# Power-Supply.net
KiCad netlist of a schematic drawn in Altium Designer
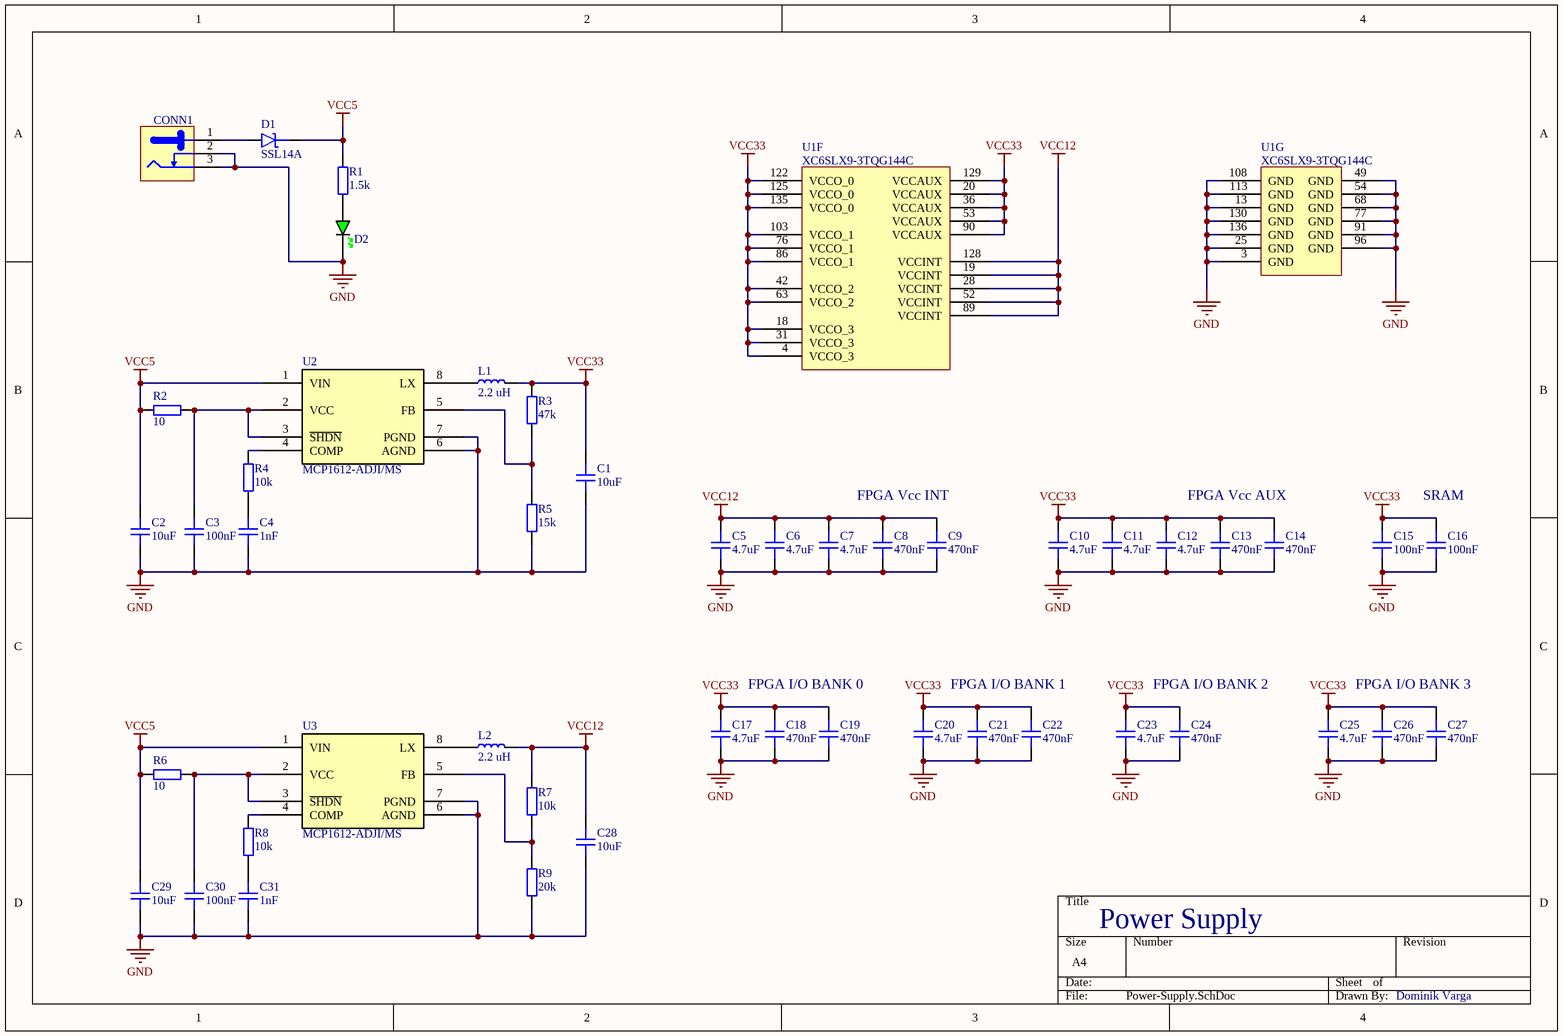
[diagram p0: Power-Supply.SchDoc]

(export (version "E")
  (design (tool "Eeschema 10.0.6"))
  (components
    (comp (ref "C1")
      (value "10uF")
      (footprint "CAP_SMD1210")
      (description "Capacitor SMD 1210")
      (libsource (lib "NES-Components") (part "CAP_1210"))
    )
    (comp (ref "C2")
      (value "10uF")
      (footprint "CAP_SMD1210")
      (description "Capacitor SMD 1210")
      (libsource (lib "NES-Components") (part "CAP_1210"))
    )
    (comp (ref "C3")
      (value "100nF")
      (footprint "CAP_SMD0603")
      (description "Capacitor SMD 0603")
      (libsource (lib "NES-Components") (part "CAP_0603"))
    )
    (comp (ref "C4")
      (value "1nF")
      (footprint "CAP_SMD0603")
      (description "Capacitor SMD 0603")
      (libsource (lib "NES-Components") (part "CAP_0603"))
    )
    (comp (ref "C5")
      (value "4.7uF")
      (footprint "CAP_SMD0603")
      (description "Capacitor SMD 0603")
      (libsource (lib "NES-Components") (part "CAP_0603"))
    )
    (comp (ref "C6")
      (value "4.7uF")
      (footprint "CAP_SMD0603")
      (description "Capacitor SMD 0603")
      (libsource (lib "NES-Components") (part "CAP_0603"))
    )
    (comp (ref "C7")
      (value "4.7uF")
      (footprint "CAP_SMD0603")
      (description "Capacitor SMD 0603")
      (libsource (lib "NES-Components") (part "CAP_0603"))
    )
    (comp (ref "C8")
      (value "470nF")
      (footprint "CAP_SMD0603")
      (description "Capacitor SMD 0603")
      (libsource (lib "NES-Components") (part "CAP_0603"))
    )
    (comp (ref "C9")
      (value "470nF")
      (footprint "CAP_SMD0603")
      (description "Capacitor SMD 0603")
      (libsource (lib "NES-Components") (part "CAP_0603"))
    )
    (comp (ref "C10")
      (value "4.7uF")
      (footprint "CAP_SMD0603")
      (description "Capacitor SMD 0603")
      (libsource (lib "NES-Components") (part "CAP_0603"))
    )
    (comp (ref "C11")
      (value "4.7uF")
      (footprint "CAP_SMD0603")
      (description "Capacitor SMD 0603")
      (libsource (lib "NES-Components") (part "CAP_0603"))
    )
    (comp (ref "C12")
      (value "4.7uF")
      (footprint "CAP_SMD0603")
      (description "Capacitor SMD 0603")
      (libsource (lib "NES-Components") (part "CAP_0603"))
    )
    (comp (ref "C13")
      (value "470nF")
      (footprint "CAP_SMD0603")
      (description "Capacitor SMD 0603")
      (libsource (lib "NES-Components") (part "CAP_0603"))
    )
    (comp (ref "C14")
      (value "470nF")
      (footprint "CAP_SMD0603")
      (description "Capacitor SMD 0603")
      (libsource (lib "NES-Components") (part "CAP_0603"))
    )
    (comp (ref "C15")
      (value "100nF")
      (footprint "CAP_SMD0603")
      (description "Capacitor SMD 0603")
      (libsource (lib "NES-Components") (part "CAP_0603"))
    )
    (comp (ref "C16")
      (value "100nF")
      (footprint "CAP_SMD0603")
      (description "Capacitor SMD 0603")
      (libsource (lib "NES-Components") (part "CAP_0603"))
    )
    (comp (ref "C17")
      (value "4.7uF")
      (footprint "CAP_SMD0603")
      (description "Capacitor SMD 0603")
      (libsource (lib "NES-Components") (part "CAP_0603"))
    )
    (comp (ref "C18")
      (value "470nF")
      (footprint "CAP_SMD0603")
      (description "Capacitor SMD 0603")
      (libsource (lib "NES-Components") (part "CAP_0603"))
    )
    (comp (ref "C19")
      (value "470nF")
      (footprint "CAP_SMD0603")
      (description "Capacitor SMD 0603")
      (libsource (lib "NES-Components") (part "CAP_0603"))
    )
    (comp (ref "C20")
      (value "4.7uF")
      (footprint "CAP_SMD0603")
      (description "Capacitor SMD 0603")
      (libsource (lib "NES-Components") (part "CAP_0603"))
    )
    (comp (ref "C21")
      (value "470nF")
      (footprint "CAP_SMD0603")
      (description "Capacitor SMD 0603")
      (libsource (lib "NES-Components") (part "CAP_0603"))
    )
    (comp (ref "C22")
      (value "470nF")
      (footprint "CAP_SMD0603")
      (description "Capacitor SMD 0603")
      (libsource (lib "NES-Components") (part "CAP_0603"))
    )
    (comp (ref "C23")
      (value "4.7uF")
      (footprint "CAP_SMD0603")
      (description "Capacitor SMD 0603")
      (libsource (lib "NES-Components") (part "CAP_0603"))
    )
    (comp (ref "C24")
      (value "470nF")
      (footprint "CAP_SMD0603")
      (description "Capacitor SMD 0603")
      (libsource (lib "NES-Components") (part "CAP_0603"))
    )
    (comp (ref "C25")
      (value "4.7uF")
      (footprint "CAP_SMD0603")
      (description "Capacitor SMD 0603")
      (libsource (lib "NES-Components") (part "CAP_0603"))
    )
    (comp (ref "C26")
      (value "470nF")
      (footprint "CAP_SMD0603")
      (description "Capacitor SMD 0603")
      (libsource (lib "NES-Components") (part "CAP_0603"))
    )
    (comp (ref "C27")
      (value "470nF")
      (footprint "CAP_SMD0603")
      (description "Capacitor SMD 0603")
      (libsource (lib "NES-Components") (part "CAP_0603"))
    )
    (comp (ref "C28")
      (value "10uF")
      (footprint "CAP_SMD1210")
      (description "Capacitor SMD 1210")
      (libsource (lib "NES-Components") (part "CAP_1210"))
    )
    (comp (ref "C29")
      (value "10uF")
      (footprint "CAP_SMD1210")
      (description "Capacitor SMD 1210")
      (libsource (lib "NES-Components") (part "CAP_1210"))
    )
    (comp (ref "C30")
      (value "100nF")
      (footprint "CAP_SMD0603")
      (description "Capacitor SMD 0603")
      (libsource (lib "NES-Components") (part "CAP_0603"))
    )
    (comp (ref "C31")
      (value "1nF")
      (footprint "CAP_SMD0603")
      (description "Capacitor SMD 0603")
      (libsource (lib "NES-Components") (part "CAP_0603"))
    )
    (comp (ref "CONN1")
      (value "DC_PWR")
      (footprint "DC_PWR_CONN")
      (description "12V /  5A, 2.1mm Diameter Pin, DC Power Socket With  Switch. DC10A Type")
      (libsource (lib "NES-Components") (part "DC_PWR"))
    )
    (comp (ref "D1")
      (value "SSL14A")
      (footprint "DIOM5226X230N")
      (description "Schottky Barrier Diode SSL14A")
      (libsource (lib "NES-Components") (part "SSL14A"))
    )
    (comp (ref "D2")
      (value "GREEN")
      (footprint "LED_G_SMD0603")
      (description "LED 0603 GREEN SMD")
      (libsource (lib "NES-Components") (part "LED_0603_GREEN"))
    )
    (comp (ref "L1")
      (value "2.2 uH")
      (footprint "SDR0604")
      (description "Inductor SDR0604")
      (libsource (lib "NES-Components") (part "SDR0604"))
    )
    (comp (ref "L2")
      (value "2.2 uH")
      (footprint "SDR0604")
      (description "Inductor SDR0604")
      (libsource (lib "NES-Components") (part "SDR0604"))
    )
    (comp (ref "R1")
      (value "1.5k")
      (footprint "RES_SMD0603")
      (description "Resistor SMD 0603")
      (libsource (lib "NES-Components") (part "RES_0603"))
    )
    (comp (ref "R2")
      (value "10")
      (footprint "RES_SMD0603")
      (description "Resistor SMD 0603")
      (libsource (lib "NES-Components") (part "RES_0603"))
    )
    (comp (ref "R3")
      (value "47k")
      (footprint "RES_SMD0603")
      (description "Resistor SMD 0603")
      (libsource (lib "NES-Components") (part "RES_0603"))
    )
    (comp (ref "R4")
      (value "10k")
      (footprint "RES_SMD0603")
      (description "Resistor SMD 0603")
      (libsource (lib "NES-Components") (part "RES_0603"))
    )
    (comp (ref "R5")
      (value "15k")
      (footprint "RES_SMD0603")
      (description "Resistor SMD 0603")
      (libsource (lib "NES-Components") (part "RES_0603"))
    )
    (comp (ref "R6")
      (value "10")
      (footprint "RES_SMD0603")
      (description "Resistor SMD 0603")
      (libsource (lib "NES-Components") (part "RES_0603"))
    )
    (comp (ref "R7")
      (value "10k")
      (footprint "RES_SMD0603")
      (description "Resistor SMD 0603")
      (libsource (lib "NES-Components") (part "RES_0603"))
    )
    (comp (ref "R8")
      (value "10k")
      (footprint "RES_SMD0603")
      (description "Resistor SMD 0603")
      (libsource (lib "NES-Components") (part "RES_0603"))
    )
    (comp (ref "R9")
      (value "20k")
      (footprint "RES_SMD0603")
      (description "Resistor SMD 0603")
      (libsource (lib "NES-Components") (part "RES_0603"))
    )
    (comp (ref "U1")
      (value "XC6SLX9-3TQG144C")
      (footprint "QFP50P2200X2200X160-144N")
      (libsource (lib "NES-Components") (part "XC6SLX9-3TQG144C"))
    )
    (comp (ref "U2")
      (value "MCP1612-ADJI/MS")
      (footprint "SOP65P490X109-8N")
      (description "Single 1A Synchronous Buck Regulator, 1.4MHz, 8-Pin MSOP, Industrial Temperature")
      (fields (field (name "COPYRIGHT") "Copyright (C) 2023 Ultra Librarian. All rights reserved."))
      (libsource (lib "NES-Components") (part "MCP1612-ADJI/MS"))
    )
    (comp (ref "U3")
      (value "MCP1612-ADJI/MS")
      (footprint "SOP65P490X109-8N")
      (description "Single 1A Synchronous Buck Regulator, 1.4MHz, 8-Pin MSOP, Industrial Temperature")
      (fields (field (name "COPYRIGHT") "Copyright (C) 2023 Ultra Librarian. All rights reserved."))
      (libsource (lib "NES-Components") (part "MCP1612-ADJI/MS"))
    )
  )
  (nets
    (net (code "1") (name "GND") (class "Default")
      (node (ref "C1") (pin "1") (pinfunction "1_1") (pintype "passive"))
      (node (ref "C10") (pin "1") (pinfunction "1_1") (pintype "passive"))
      (node (ref "C11") (pin "1") (pinfunction "1_1") (pintype "passive"))
      (node (ref "C12") (pin "1") (pinfunction "1_1") (pintype "passive"))
      (node (ref "C13") (pin "1") (pinfunction "1_1") (pintype "passive"))
      (node (ref "C14") (pin "1") (pinfunction "1_1") (pintype "passive"))
      (node (ref "C15") (pin "1") (pinfunction "1_1") (pintype "passive"))
      (node (ref "C16") (pin "1") (pinfunction "1_1") (pintype "passive"))
      (node (ref "C17") (pin "1") (pinfunction "1_1") (pintype "passive"))
      (node (ref "C18") (pin "1") (pinfunction "1_1") (pintype "passive"))
      (node (ref "C19") (pin "1") (pinfunction "1_1") (pintype "passive"))
      (node (ref "C2") (pin "1") (pinfunction "1_1") (pintype "passive"))
      (node (ref "C20") (pin "1") (pinfunction "1_1") (pintype "passive"))
      (node (ref "C21") (pin "1") (pinfunction "1_1") (pintype "passive"))
      (node (ref "C22") (pin "1") (pinfunction "1_1") (pintype "passive"))
      (node (ref "C23") (pin "1") (pinfunction "1_1") (pintype "passive"))
      (node (ref "C24") (pin "1") (pinfunction "1_1") (pintype "passive"))
      (node (ref "C25") (pin "1") (pinfunction "1_1") (pintype "passive"))
      (node (ref "C26") (pin "1") (pinfunction "1_1") (pintype "passive"))
      (node (ref "C27") (pin "1") (pinfunction "1_1") (pintype "passive"))
      (node (ref "C28") (pin "1") (pinfunction "1_1") (pintype "passive"))
      (node (ref "C29") (pin "1") (pinfunction "1_1") (pintype "passive"))
      (node (ref "C3") (pin "1") (pinfunction "1_1") (pintype "passive"))
      (node (ref "C30") (pin "1") (pinfunction "1_1") (pintype "passive"))
      (node (ref "C31") (pin "1") (pinfunction "1_1") (pintype "passive"))
      (node (ref "C4") (pin "1") (pinfunction "1_1") (pintype "passive"))
      (node (ref "C5") (pin "1") (pinfunction "1_1") (pintype "passive"))
      (node (ref "C6") (pin "1") (pinfunction "1_1") (pintype "passive"))
      (node (ref "C7") (pin "1") (pinfunction "1_1") (pintype "passive"))
      (node (ref "C8") (pin "1") (pinfunction "1_1") (pintype "passive"))
      (node (ref "C9") (pin "1") (pinfunction "1_1") (pintype "passive"))
      (node (ref "CONN1") (pin "2") (pinfunction "2_2") (pintype "power_in"))
      (node (ref "CONN1") (pin "3") (pinfunction "3_3") (pintype "power_in"))
      (node (ref "D2") (pin "2") (pinfunction "K_2") (pintype "passive"))
      (node (ref "R5") (pin "1") (pinfunction "1_1") (pintype "passive"))
      (node (ref "R9") (pin "1") (pinfunction "1_1") (pintype "passive"))
      (node (ref "U1") (pin "108") (pinfunction "GND_108") (pintype "power_in"))
      (node (ref "U1") (pin "113") (pinfunction "GND_113") (pintype "power_in"))
      (node (ref "U1") (pin "13") (pinfunction "GND_13") (pintype "power_in"))
      (node (ref "U1") (pin "130") (pinfunction "GND_130") (pintype "power_in"))
      (node (ref "U1") (pin "136") (pinfunction "GND_136") (pintype "power_in"))
      (node (ref "U1") (pin "25") (pinfunction "GND_25") (pintype "power_in"))
      (node (ref "U1") (pin "3") (pinfunction "GND_3") (pintype "power_in"))
      (node (ref "U1") (pin "49") (pinfunction "GND_49") (pintype "power_in"))
      (node (ref "U1") (pin "54") (pinfunction "GND_54") (pintype "power_in"))
      (node (ref "U1") (pin "68") (pinfunction "GND_68") (pintype "power_in"))
      (node (ref "U1") (pin "77") (pinfunction "GND_77") (pintype "power_in"))
      (node (ref "U1") (pin "91") (pinfunction "GND_91") (pintype "power_in"))
      (node (ref "U1") (pin "96") (pinfunction "GND_96") (pintype "power_in"))
      (node (ref "U2") (pin "6") (pinfunction "AGND_6") (pintype "passive"))
      (node (ref "U2") (pin "7") (pinfunction "PGND_7") (pintype "passive"))
      (node (ref "U3") (pin "6") (pinfunction "AGND_6") (pintype "passive"))
      (node (ref "U3") (pin "7") (pinfunction "PGND_7") (pintype "passive"))
    )
    (net (code "2") (name "Net-(C4-Pad2)") (class "Default")
      (node (ref "C4") (pin "2") (pinfunction "2_2") (pintype "passive"))
      (node (ref "R4") (pin "1") (pinfunction "1_1") (pintype "passive"))
    )
    (net (code "3") (name "Net-(C31-Pad2)") (class "Default")
      (node (ref "C31") (pin "2") (pinfunction "2_2") (pintype "passive"))
      (node (ref "R8") (pin "1") (pinfunction "1_1") (pintype "passive"))
    )
    (net (code "4") (name "Net-(D1-A)") (class "Default")
      (node (ref "CONN1") (pin "1") (pinfunction "1_1") (pintype "power_in"))
      (node (ref "D1") (pin "2") (pinfunction "A_2") (pintype "passive"))
    )
    (net (code "5") (name "Net-(D2-A)") (class "Default")
      (node (ref "D2") (pin "1") (pinfunction "A_1") (pintype "passive"))
      (node (ref "R1") (pin "1") (pinfunction "1_1") (pintype "passive"))
    )
    (net (code "6") (name "Net-(U2-COMP)") (class "Default")
      (node (ref "R4") (pin "2") (pinfunction "2_2") (pintype "passive"))
      (node (ref "U2") (pin "4") (pinfunction "COMP_4") (pintype "passive"))
    )
    (net (code "7") (name "Net-(U2-FB)") (class "Default")
      (node (ref "R3") (pin "1") (pinfunction "1_1") (pintype "passive"))
      (node (ref "R5") (pin "2") (pinfunction "2_2") (pintype "passive"))
      (node (ref "U2") (pin "5") (pinfunction "FB_5") (pintype "passive"))
    )
    (net (code "8") (name "Net-(U2-LX)") (class "Default")
      (node (ref "L1") (pin "1") (pinfunction "1_1") (pintype "passive"))
      (node (ref "U2") (pin "8") (pinfunction "LX_8") (pintype "passive"))
    )
    (net (code "9") (name "Net-(U2-VCC)") (class "Default")
      (node (ref "C3") (pin "2") (pinfunction "2_2") (pintype "passive"))
      (node (ref "R2") (pin "2") (pinfunction "2_2") (pintype "passive"))
      (node (ref "U2") (pin "2") (pinfunction "VCC_2") (pintype "passive"))
      (node (ref "U2") (pin "3") (pinfunction "~{SHDN}_3") (pintype "passive"))
    )
    (net (code "10") (name "Net-(U3-COMP)") (class "Default")
      (node (ref "R8") (pin "2") (pinfunction "2_2") (pintype "passive"))
      (node (ref "U3") (pin "4") (pinfunction "COMP_4") (pintype "passive"))
    )
    (net (code "11") (name "Net-(U3-FB)") (class "Default")
      (node (ref "R7") (pin "1") (pinfunction "1_1") (pintype "passive"))
      (node (ref "R9") (pin "2") (pinfunction "2_2") (pintype "passive"))
      (node (ref "U3") (pin "5") (pinfunction "FB_5") (pintype "passive"))
    )
    (net (code "12") (name "Net-(U3-LX)") (class "Default")
      (node (ref "L2") (pin "1") (pinfunction "1_1") (pintype "passive"))
      (node (ref "U3") (pin "8") (pinfunction "LX_8") (pintype "passive"))
    )
    (net (code "13") (name "Net-(U3-VCC)") (class "Default")
      (node (ref "C30") (pin "2") (pinfunction "2_2") (pintype "passive"))
      (node (ref "R6") (pin "2") (pinfunction "2_2") (pintype "passive"))
      (node (ref "U3") (pin "2") (pinfunction "VCC_2") (pintype "passive"))
      (node (ref "U3") (pin "3") (pinfunction "~{SHDN}_3") (pintype "passive"))
    )
    (net (code "14") (name "VCC5") (class "Default")
      (node (ref "C2") (pin "2") (pinfunction "2_2") (pintype "passive"))
      (node (ref "C29") (pin "2") (pinfunction "2_2") (pintype "passive"))
      (node (ref "D1") (pin "1") (pinfunction "K_1") (pintype "passive"))
      (node (ref "R1") (pin "2") (pinfunction "2_2") (pintype "passive"))
      (node (ref "R2") (pin "1") (pinfunction "1_1") (pintype "passive"))
      (node (ref "R6") (pin "1") (pinfunction "1_1") (pintype "passive"))
      (node (ref "U2") (pin "1") (pinfunction "VIN_1") (pintype "passive"))
      (node (ref "U3") (pin "1") (pinfunction "VIN_1") (pintype "passive"))
    )
    (net (code "15") (name "VCC12") (class "Default")
      (node (ref "C28") (pin "2") (pinfunction "2_2") (pintype "passive"))
      (node (ref "C5") (pin "2") (pinfunction "2_2") (pintype "passive"))
      (node (ref "C6") (pin "2") (pinfunction "2_2") (pintype "passive"))
      (node (ref "C7") (pin "2") (pinfunction "2_2") (pintype "passive"))
      (node (ref "C8") (pin "2") (pinfunction "2_2") (pintype "passive"))
      (node (ref "C9") (pin "2") (pinfunction "2_2") (pintype "passive"))
      (node (ref "L2") (pin "2") (pinfunction "2_2") (pintype "passive"))
      (node (ref "R7") (pin "2") (pinfunction "2_2") (pintype "passive"))
      (node (ref "U1") (pin "128") (pinfunction "VCCINT_128") (pintype "power_in"))
      (node (ref "U1") (pin "19") (pinfunction "VCCINT_19") (pintype "power_in"))
      (node (ref "U1") (pin "28") (pinfunction "VCCINT_28") (pintype "power_in"))
      (node (ref "U1") (pin "52") (pinfunction "VCCINT_52") (pintype "power_in"))
      (node (ref "U1") (pin "89") (pinfunction "VCCINT_89") (pintype "power_in"))
    )
    (net (code "16") (name "VCC33") (class "Default")
      (node (ref "C1") (pin "2") (pinfunction "2_2") (pintype "passive"))
      (node (ref "C10") (pin "2") (pinfunction "2_2") (pintype "passive"))
      (node (ref "C11") (pin "2") (pinfunction "2_2") (pintype "passive"))
      (node (ref "C12") (pin "2") (pinfunction "2_2") (pintype "passive"))
      (node (ref "C13") (pin "2") (pinfunction "2_2") (pintype "passive"))
      (node (ref "C14") (pin "2") (pinfunction "2_2") (pintype "passive"))
      (node (ref "C15") (pin "2") (pinfunction "2_2") (pintype "passive"))
      (node (ref "C16") (pin "2") (pinfunction "2_2") (pintype "passive"))
      (node (ref "C17") (pin "2") (pinfunction "2_2") (pintype "passive"))
      (node (ref "C18") (pin "2") (pinfunction "2_2") (pintype "passive"))
      (node (ref "C19") (pin "2") (pinfunction "2_2") (pintype "passive"))
      (node (ref "C20") (pin "2") (pinfunction "2_2") (pintype "passive"))
      (node (ref "C21") (pin "2") (pinfunction "2_2") (pintype "passive"))
      (node (ref "C22") (pin "2") (pinfunction "2_2") (pintype "passive"))
      (node (ref "C23") (pin "2") (pinfunction "2_2") (pintype "passive"))
      (node (ref "C24") (pin "2") (pinfunction "2_2") (pintype "passive"))
      (node (ref "C25") (pin "2") (pinfunction "2_2") (pintype "passive"))
      (node (ref "C26") (pin "2") (pinfunction "2_2") (pintype "passive"))
      (node (ref "C27") (pin "2") (pinfunction "2_2") (pintype "passive"))
      (node (ref "L1") (pin "2") (pinfunction "2_2") (pintype "passive"))
      (node (ref "R3") (pin "2") (pinfunction "2_2") (pintype "passive"))
      (node (ref "U1") (pin "103") (pinfunction "VCCO_1_103") (pintype "power_in"))
      (node (ref "U1") (pin "122") (pinfunction "VCCO_0_122") (pintype "power_in"))
      (node (ref "U1") (pin "125") (pinfunction "VCCO_0_125") (pintype "power_in"))
      (node (ref "U1") (pin "129") (pinfunction "VCCAUX_129") (pintype "power_in"))
      (node (ref "U1") (pin "135") (pinfunction "VCCO_0_135") (pintype "power_in"))
      (node (ref "U1") (pin "18") (pinfunction "VCCO_3_18") (pintype "power_in"))
      (node (ref "U1") (pin "20") (pinfunction "VCCAUX_20") (pintype "power_in"))
      (node (ref "U1") (pin "31") (pinfunction "VCCO_3_31") (pintype "power_in"))
      (node (ref "U1") (pin "36") (pinfunction "VCCAUX_36") (pintype "power_in"))
      (node (ref "U1") (pin "4") (pinfunction "VCCO_3_4") (pintype "power_in"))
      (node (ref "U1") (pin "42") (pinfunction "VCCO_2_42") (pintype "power_in"))
      (node (ref "U1") (pin "53") (pinfunction "VCCAUX_53") (pintype "power_in"))
      (node (ref "U1") (pin "63") (pinfunction "VCCO_2_63") (pintype "power_in"))
      (node (ref "U1") (pin "76") (pinfunction "VCCO_1_76") (pintype "power_in"))
      (node (ref "U1") (pin "86") (pinfunction "VCCO_1_86") (pintype "power_in"))
      (node (ref "U1") (pin "90") (pinfunction "VCCAUX_90") (pintype "power_in"))
    )
  )
)
